# screw-front-a-1.net
KiCad netlist of a schematic drawn in EAGLE
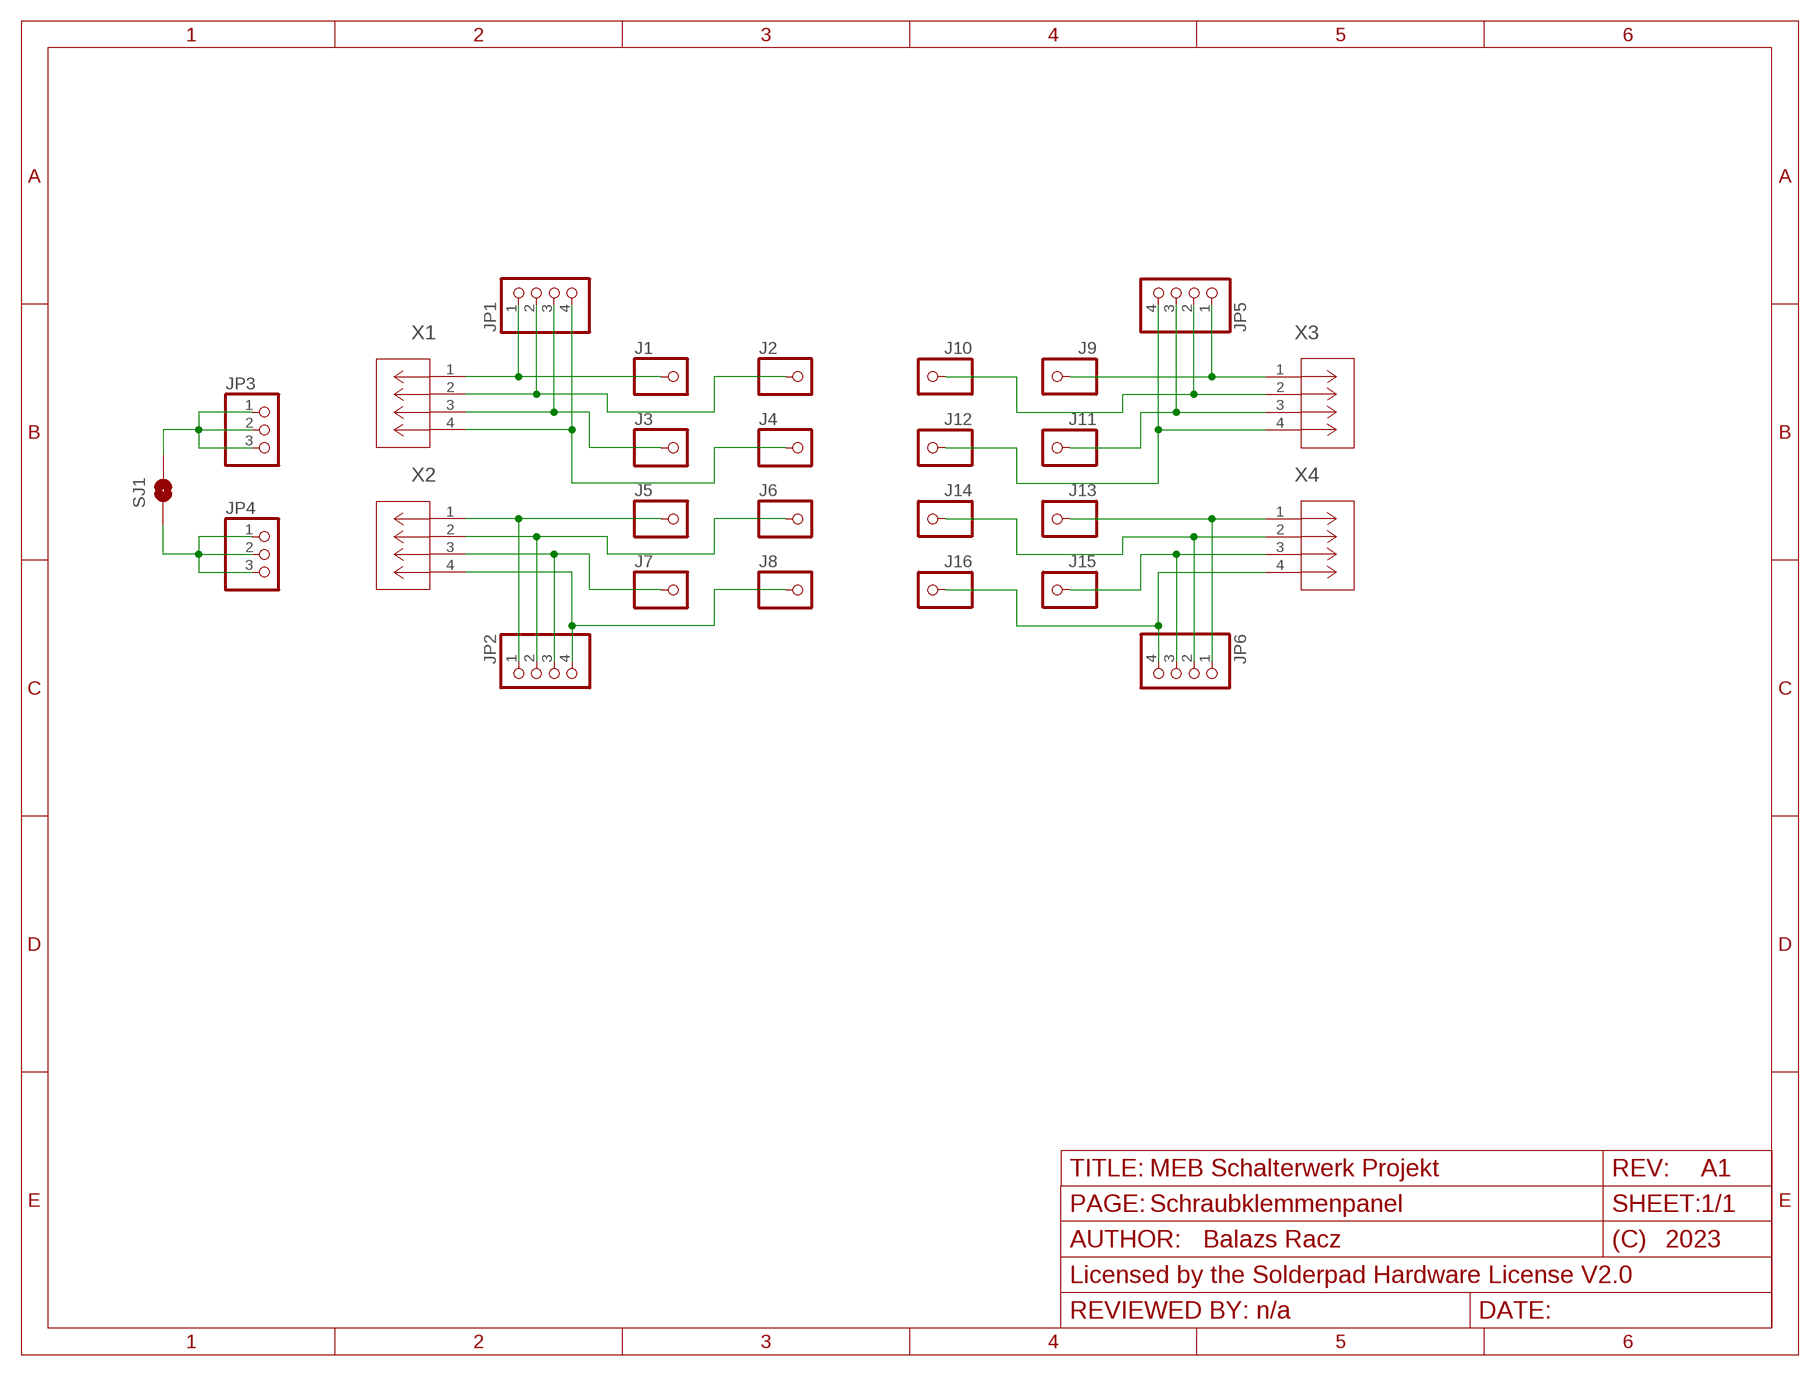
[diagram p0: schematic, sheet 1]

(export (version "E")
  (design (tool "Eeschema 10.0.6"))
  (components
    (comp (ref "J1")
      (value "M4-SCREW-HOLE")
      (footprint "eagle-import:M4-SCREW-HOLE")
      (libsource (lib "eagle-import") (part "M4-SCREW-HOLE"))
    )
    (comp (ref "J2")
      (value "M4-SCREW-HOLE")
      (footprint "eagle-import:M4-SCREW-HOLE")
      (libsource (lib "eagle-import") (part "M4-SCREW-HOLE"))
    )
    (comp (ref "J3")
      (value "M4-SCREW-HOLE")
      (footprint "eagle-import:M4-SCREW-HOLE")
      (libsource (lib "eagle-import") (part "M4-SCREW-HOLE"))
    )
    (comp (ref "J4")
      (value "M4-SCREW-HOLE")
      (footprint "eagle-import:M4-SCREW-HOLE")
      (libsource (lib "eagle-import") (part "M4-SCREW-HOLE"))
    )
    (comp (ref "J5")
      (value "M4-SCREW-HOLE")
      (footprint "eagle-import:M4-SCREW-HOLE")
      (libsource (lib "eagle-import") (part "M4-SCREW-HOLE"))
    )
    (comp (ref "J6")
      (value "M4-SCREW-HOLE")
      (footprint "eagle-import:M4-SCREW-HOLE")
      (libsource (lib "eagle-import") (part "M4-SCREW-HOLE"))
    )
    (comp (ref "J7")
      (value "M4-SCREW-HOLE")
      (footprint "eagle-import:M4-SCREW-HOLE")
      (libsource (lib "eagle-import") (part "M4-SCREW-HOLE"))
    )
    (comp (ref "J8")
      (value "M4-SCREW-HOLE")
      (footprint "eagle-import:M4-SCREW-HOLE")
      (libsource (lib "eagle-import") (part "M4-SCREW-HOLE"))
    )
    (comp (ref "J9")
      (value "M4-SCREW-HOLE")
      (footprint "eagle-import:M4-SCREW-HOLE")
      (libsource (lib "eagle-import") (part "M4-SCREW-HOLE"))
    )
    (comp (ref "J10")
      (value "M4-SCREW-HOLE")
      (footprint "eagle-import:M4-SCREW-HOLE")
      (libsource (lib "eagle-import") (part "M4-SCREW-HOLE"))
    )
    (comp (ref "J11")
      (value "M4-SCREW-HOLE")
      (footprint "eagle-import:M4-SCREW-HOLE")
      (libsource (lib "eagle-import") (part "M4-SCREW-HOLE"))
    )
    (comp (ref "J12")
      (value "M4-SCREW-HOLE")
      (footprint "eagle-import:M4-SCREW-HOLE")
      (libsource (lib "eagle-import") (part "M4-SCREW-HOLE"))
    )
    (comp (ref "J13")
      (value "M4-SCREW-HOLE")
      (footprint "eagle-import:M4-SCREW-HOLE")
      (libsource (lib "eagle-import") (part "M4-SCREW-HOLE"))
    )
    (comp (ref "J14")
      (value "M4-SCREW-HOLE")
      (footprint "eagle-import:M4-SCREW-HOLE")
      (libsource (lib "eagle-import") (part "M4-SCREW-HOLE"))
    )
    (comp (ref "J15")
      (value "M4-SCREW-HOLE")
      (footprint "eagle-import:M4-SCREW-HOLE")
      (libsource (lib "eagle-import") (part "M4-SCREW-HOLE"))
    )
    (comp (ref "J16")
      (value "M4-SCREW-HOLE")
      (footprint "eagle-import:M4-SCREW-HOLE")
      (libsource (lib "eagle-import") (part "M4-SCREW-HOLE"))
    )
    (comp (ref "JP1")
      (value "PINHD-1X4")
      (footprint "eagle-import:1X04")
      (libsource (lib "eagle-import") (part "PINHD-1X4"))
    )
    (comp (ref "JP2")
      (value "PINHD-1X4")
      (footprint "eagle-import:1X04")
      (libsource (lib "eagle-import") (part "PINHD-1X4"))
    )
    (comp (ref "JP3")
      (value "PINHD-1X3")
      (footprint "eagle-import:1X03")
      (libsource (lib "eagle-import") (part "PINHD-1X3"))
    )
    (comp (ref "JP4")
      (value "PINHD-1X3")
      (footprint "eagle-import:1X03")
      (libsource (lib "eagle-import") (part "PINHD-1X3"))
    )
    (comp (ref "JP5")
      (value "PINHD-1X4")
      (footprint "eagle-import:1X04")
      (libsource (lib "eagle-import") (part "PINHD-1X4"))
    )
    (comp (ref "JP6")
      (value "PINHD-1X4")
      (footprint "eagle-import:1X04")
      (libsource (lib "eagle-import") (part "PINHD-1X4"))
    )
    (comp (ref "SJ1")
      (value "SJRND2")
      (footprint "eagle-import:SJ_RND2")
      (libsource (lib "eagle-import") (part "SJRND2"))
    )
    (comp (ref "X1")
      (value "PHNX_4P_350CONN_1984989_PXC")
      (footprint "eagle-import:PHNX_4P_350")
      (fields
        (field (name "MANUFACTURER_PART_NUMBER") "1984989")
        (field (name "COPYRIGHT") "Copyright (C) 2023 Ultra Librarian. All rights reserved.")
      )
      (libsource (lib "eagle-import") (part "PHNX_4P_350CONN_1984989_PXC"))
    )
    (comp (ref "X2")
      (value "PHNX_4P_350CONN_1984989_PXC")
      (footprint "eagle-import:PHNX_4P_350")
      (fields
        (field (name "MANUFACTURER_PART_NUMBER") "1984989")
        (field (name "COPYRIGHT") "Copyright (C) 2023 Ultra Librarian. All rights reserved.")
      )
      (libsource (lib "eagle-import") (part "PHNX_4P_350CONN_1984989_PXC"))
    )
    (comp (ref "X3")
      (value "PHNX_4P_350CONN_1984989_PXC")
      (footprint "eagle-import:PHNX_4P_350")
      (fields
        (field (name "MANUFACTURER_PART_NUMBER") "1984989")
        (field (name "COPYRIGHT") "Copyright (C) 2023 Ultra Librarian. All rights reserved.")
      )
      (libsource (lib "eagle-import") (part "PHNX_4P_350CONN_1984989_PXC"))
    )
    (comp (ref "X4")
      (value "PHNX_4P_350CONN_1984989_PXC")
      (footprint "eagle-import:PHNX_4P_350")
      (fields
        (field (name "MANUFACTURER_PART_NUMBER") "1984989")
        (field (name "COPYRIGHT") "Copyright (C) 2023 Ultra Librarian. All rights reserved.")
      )
      (libsource (lib "eagle-import") (part "PHNX_4P_350CONN_1984989_PXC"))
    )
  )
  (nets
    (net (code "1") (name "Net-(J1-1)") (class "Default")
      (node (ref "J1") (pin "P$1") (pinfunction "1_P$1") (pintype "passive"))
      (node (ref "JP1") (pin "1") (pinfunction "1_1") (pintype "passive"))
      (node (ref "X1") (pin "1") (pinfunction "1_1") (pintype "passive"))
    )
    (net (code "2") (name "Net-(J2-1)") (class "Default")
      (node (ref "J2") (pin "P$1") (pinfunction "1_P$1") (pintype "passive"))
      (node (ref "JP1") (pin "2") (pinfunction "2_2") (pintype "passive"))
      (node (ref "X1") (pin "2") (pinfunction "2_2") (pintype "passive"))
    )
    (net (code "3") (name "Net-(J3-1)") (class "Default")
      (node (ref "J3") (pin "P$1") (pinfunction "1_P$1") (pintype "passive"))
      (node (ref "JP1") (pin "3") (pinfunction "3_3") (pintype "passive"))
      (node (ref "X1") (pin "3") (pinfunction "3_3") (pintype "passive"))
    )
    (net (code "4") (name "Net-(J4-1)") (class "Default")
      (node (ref "J4") (pin "P$1") (pinfunction "1_P$1") (pintype "passive"))
      (node (ref "JP1") (pin "4") (pinfunction "4_4") (pintype "passive"))
      (node (ref "X1") (pin "4") (pinfunction "4_4") (pintype "passive"))
    )
    (net (code "5") (name "Net-(J5-1)") (class "Default")
      (node (ref "J5") (pin "P$1") (pinfunction "1_P$1") (pintype "passive"))
      (node (ref "JP2") (pin "1") (pinfunction "1_1") (pintype "passive"))
      (node (ref "X2") (pin "1") (pinfunction "1_1") (pintype "passive"))
    )
    (net (code "6") (name "Net-(J6-1)") (class "Default")
      (node (ref "J6") (pin "P$1") (pinfunction "1_P$1") (pintype "passive"))
      (node (ref "JP2") (pin "2") (pinfunction "2_2") (pintype "passive"))
      (node (ref "X2") (pin "2") (pinfunction "2_2") (pintype "passive"))
    )
    (net (code "7") (name "Net-(J7-1)") (class "Default")
      (node (ref "J7") (pin "P$1") (pinfunction "1_P$1") (pintype "passive"))
      (node (ref "JP2") (pin "3") (pinfunction "3_3") (pintype "passive"))
      (node (ref "X2") (pin "3") (pinfunction "3_3") (pintype "passive"))
    )
    (net (code "8") (name "Net-(J8-1)") (class "Default")
      (node (ref "J8") (pin "P$1") (pinfunction "1_P$1") (pintype "passive"))
      (node (ref "JP2") (pin "4") (pinfunction "4_4") (pintype "passive"))
      (node (ref "X2") (pin "4") (pinfunction "4_4") (pintype "passive"))
    )
    (net (code "9") (name "Net-(J9-1)") (class "Default")
      (node (ref "J9") (pin "P$1") (pinfunction "1_P$1") (pintype "passive"))
      (node (ref "JP5") (pin "1") (pinfunction "1_1") (pintype "passive"))
      (node (ref "X3") (pin "1") (pinfunction "1_1") (pintype "passive"))
    )
    (net (code "10") (name "Net-(J10-1)") (class "Default")
      (node (ref "J10") (pin "P$1") (pinfunction "1_P$1") (pintype "passive"))
      (node (ref "JP5") (pin "2") (pinfunction "2_2") (pintype "passive"))
      (node (ref "X3") (pin "2") (pinfunction "2_2") (pintype "passive"))
    )
    (net (code "11") (name "Net-(J11-1)") (class "Default")
      (node (ref "J11") (pin "P$1") (pinfunction "1_P$1") (pintype "passive"))
      (node (ref "JP5") (pin "3") (pinfunction "3_3") (pintype "passive"))
      (node (ref "X3") (pin "3") (pinfunction "3_3") (pintype "passive"))
    )
    (net (code "12") (name "Net-(J12-1)") (class "Default")
      (node (ref "J12") (pin "P$1") (pinfunction "1_P$1") (pintype "passive"))
      (node (ref "JP5") (pin "4") (pinfunction "4_4") (pintype "passive"))
      (node (ref "X3") (pin "4") (pinfunction "4_4") (pintype "passive"))
    )
    (net (code "13") (name "Net-(J13-1)") (class "Default")
      (node (ref "J13") (pin "P$1") (pinfunction "1_P$1") (pintype "passive"))
      (node (ref "JP6") (pin "1") (pinfunction "1_1") (pintype "passive"))
      (node (ref "X4") (pin "1") (pinfunction "1_1") (pintype "passive"))
    )
    (net (code "14") (name "Net-(J14-1)") (class "Default")
      (node (ref "J14") (pin "P$1") (pinfunction "1_P$1") (pintype "passive"))
      (node (ref "JP6") (pin "2") (pinfunction "2_2") (pintype "passive"))
      (node (ref "X4") (pin "2") (pinfunction "2_2") (pintype "passive"))
    )
    (net (code "15") (name "Net-(J15-1)") (class "Default")
      (node (ref "J15") (pin "P$1") (pinfunction "1_P$1") (pintype "passive"))
      (node (ref "JP6") (pin "3") (pinfunction "3_3") (pintype "passive"))
      (node (ref "X4") (pin "3") (pinfunction "3_3") (pintype "passive"))
    )
    (net (code "16") (name "Net-(J16-1)") (class "Default")
      (node (ref "J16") (pin "P$1") (pinfunction "1_P$1") (pintype "passive"))
      (node (ref "JP6") (pin "4") (pinfunction "4_4") (pintype "passive"))
      (node (ref "X4") (pin "4") (pinfunction "4_4") (pintype "passive"))
    )
    (net (code "17") (name "Net-(SJ1-1)") (class "Default")
      (node (ref "JP4") (pin "1") (pinfunction "1_1") (pintype "passive"))
      (node (ref "JP4") (pin "2") (pinfunction "2_2") (pintype "passive"))
      (node (ref "JP4") (pin "3") (pinfunction "3_3") (pintype "passive"))
      (node (ref "SJ1") (pin "P$1") (pinfunction "1_P$1") (pintype "passive"))
    )
    (net (code "18") (name "Net-(SJ1-2)") (class "Default")
      (node (ref "JP3") (pin "1") (pinfunction "1_1") (pintype "passive"))
      (node (ref "JP3") (pin "2") (pinfunction "2_2") (pintype "passive"))
      (node (ref "JP3") (pin "3") (pinfunction "3_3") (pintype "passive"))
      (node (ref "SJ1") (pin "P$2") (pinfunction "2_P$2") (pintype "passive"))
    )
  )
)
